# FPGA_Decoupling.net
KiCad netlist of a schematic drawn in Altium Designer
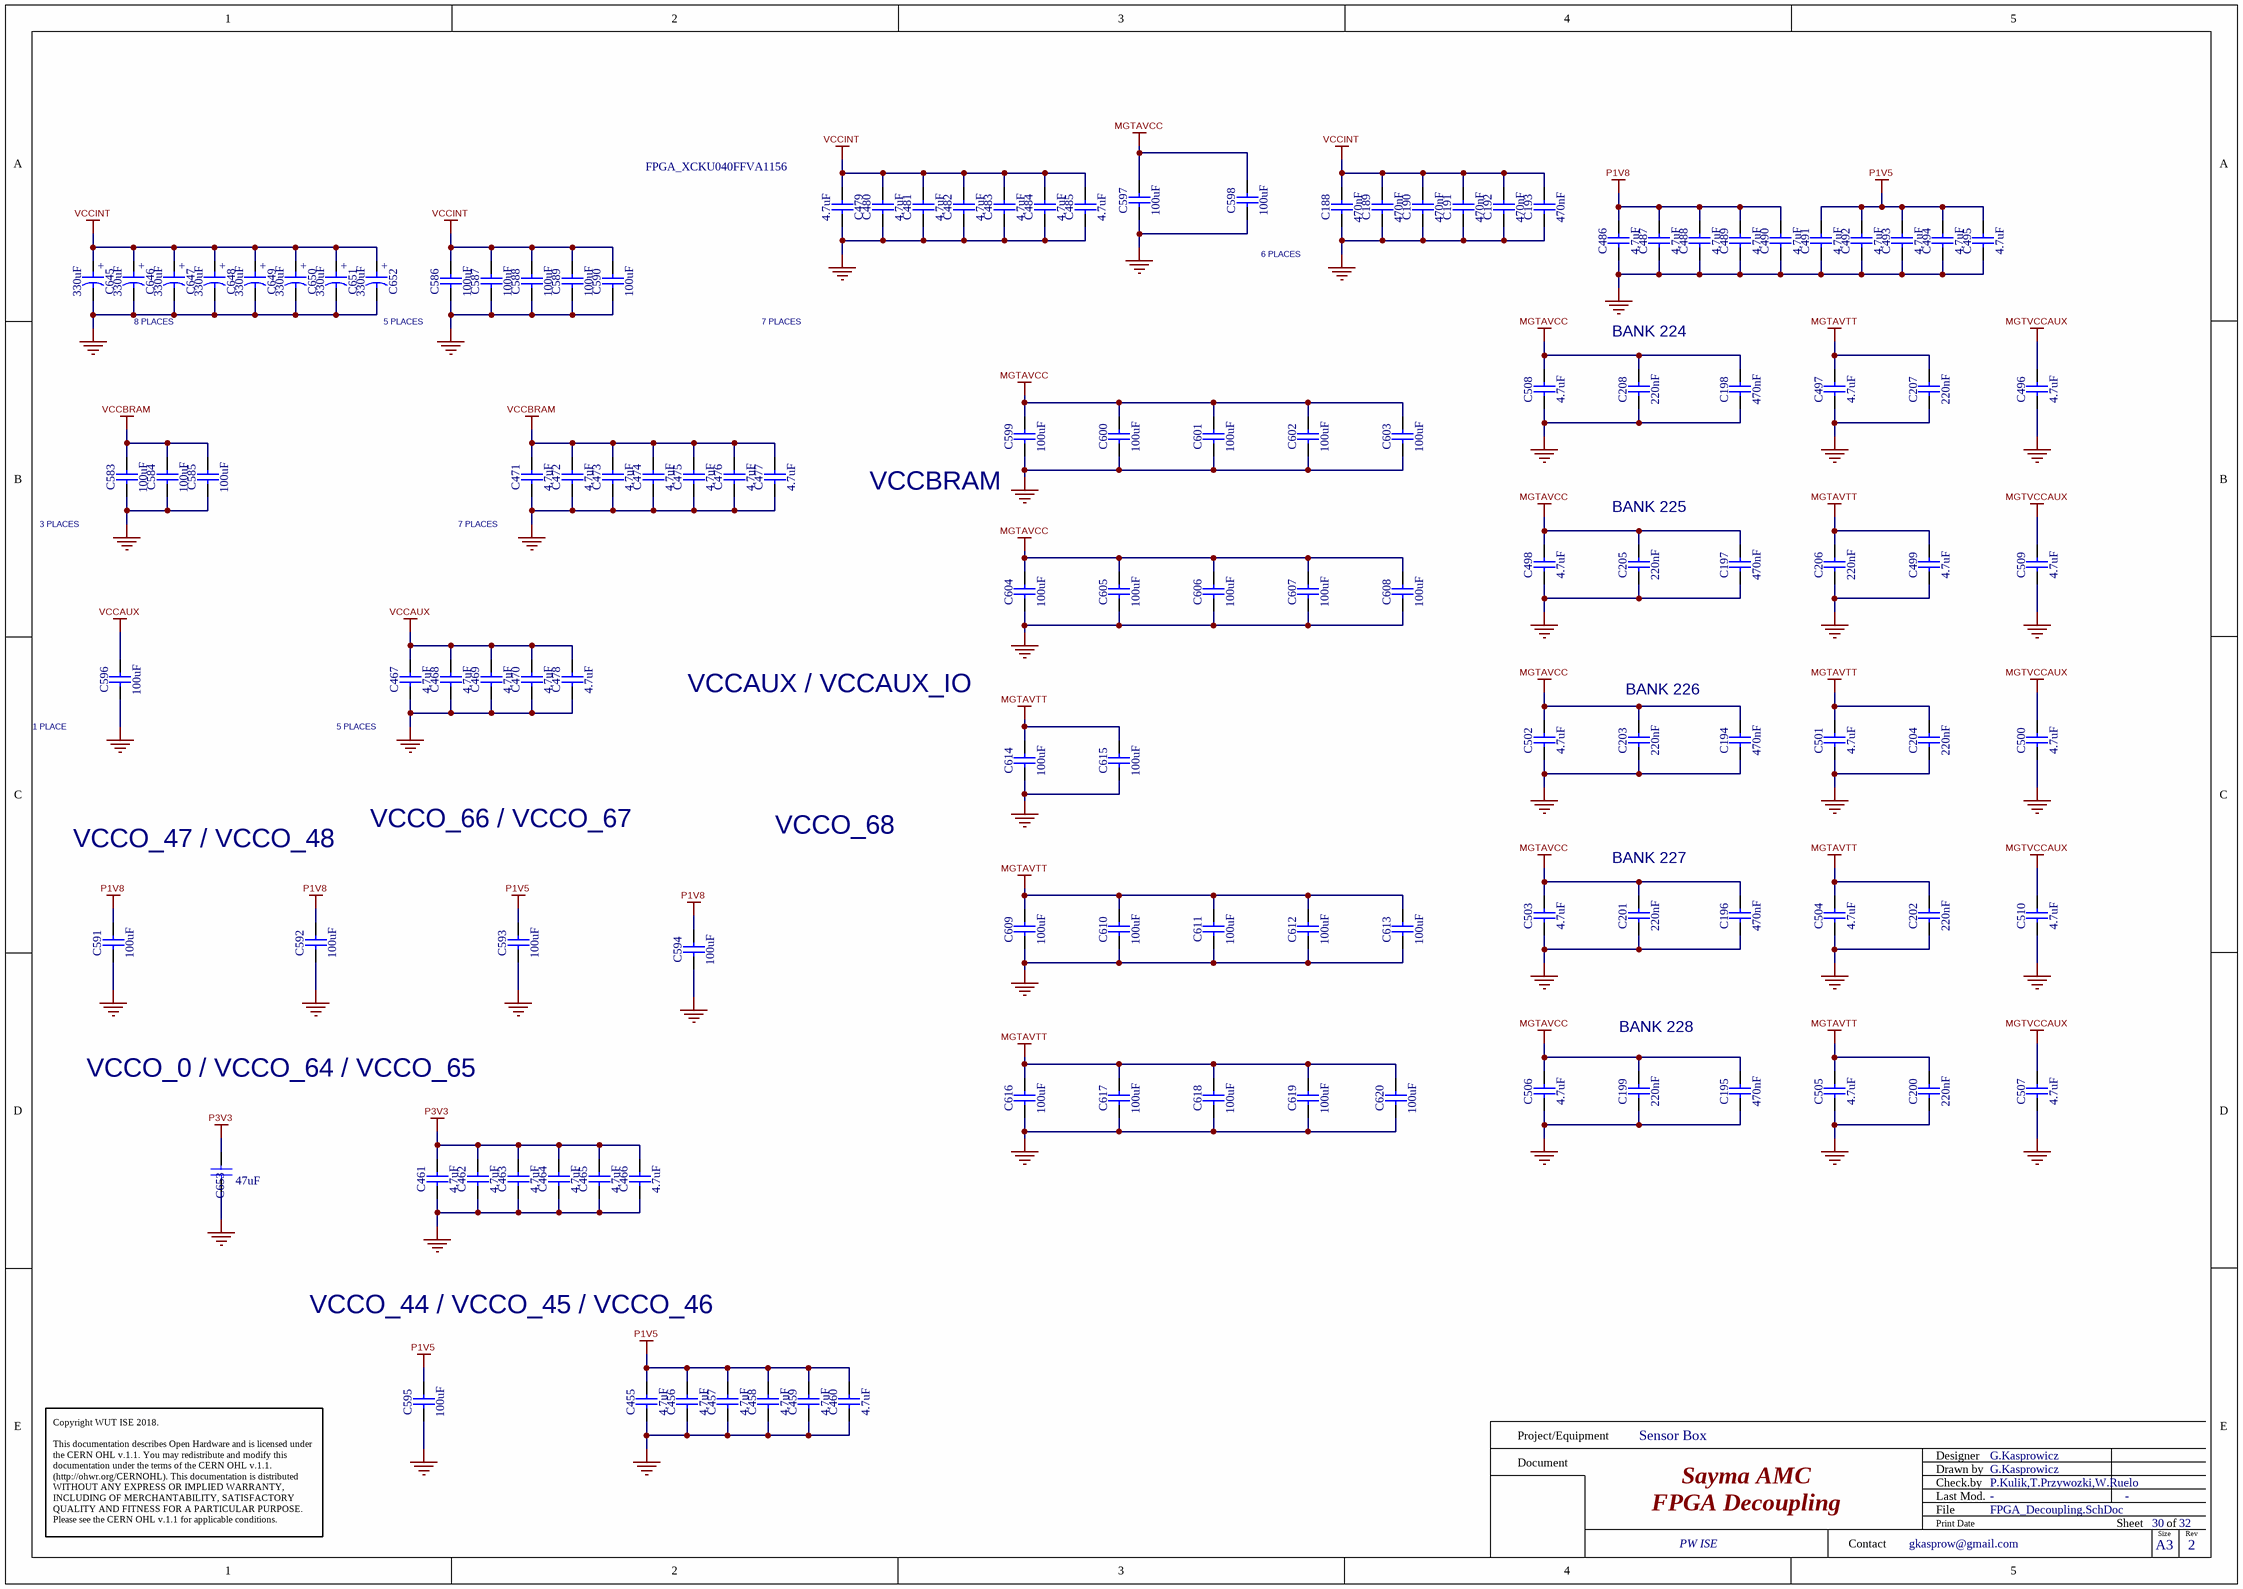
[diagram p0: FPGA_Decoupling.SchDoc]

(export (version "E")
  (design (tool "Eeschema 10.0.6"))
  (components
    (comp (ref "C188")
      (value "470nF")
      (footprint "CAPC0603X33N")
      (description "Non-polarised capacitor")
      (fields
        (field (name "MANUFACTURER PART NUMBER") "CC0201_470NF_4V_20%_X5R")
        (field (name "MANUFACTURER") "GENERIC")
        (field (name "AUTHOR") "CERN DEM JLC")
      )
      (libsource (lib "Capacitors") (part "Capacitor - non polarized"))
    )
    (comp (ref "C189")
      (value "470nF")
      (footprint "CAPC0603X33N")
      (description "Non-polarised capacitor")
      (fields
        (field (name "MANUFACTURER PART NUMBER") "CC0201_470NF_4V_20%_X5R")
        (field (name "MANUFACTURER") "GENERIC")
        (field (name "AUTHOR") "CERN DEM JLC")
      )
      (libsource (lib "Capacitors") (part "Capacitor - non polarized"))
    )
    (comp (ref "C190")
      (value "470nF")
      (footprint "CAPC0603X33N")
      (description "Non-polarised capacitor")
      (fields
        (field (name "MANUFACTURER PART NUMBER") "CC0201_470NF_4V_20%_X5R")
        (field (name "MANUFACTURER") "GENERIC")
        (field (name "AUTHOR") "CERN DEM JLC")
      )
      (libsource (lib "Capacitors") (part "Capacitor - non polarized"))
    )
    (comp (ref "C191")
      (value "470nF")
      (footprint "CAPC0603X33N")
      (description "Non-polarised capacitor")
      (fields
        (field (name "MANUFACTURER PART NUMBER") "CC0201_470NF_4V_20%_X5R")
        (field (name "MANUFACTURER") "GENERIC")
        (field (name "AUTHOR") "CERN DEM JLC")
      )
      (libsource (lib "Capacitors") (part "Capacitor - non polarized"))
    )
    (comp (ref "C192")
      (value "470nF")
      (footprint "CAPC0603X33N")
      (description "Non-polarised capacitor")
      (fields
        (field (name "MANUFACTURER PART NUMBER") "CC0201_470NF_4V_20%_X5R")
        (field (name "MANUFACTURER") "GENERIC")
        (field (name "AUTHOR") "CERN DEM JLC")
      )
      (libsource (lib "Capacitors") (part "Capacitor - non polarized"))
    )
    (comp (ref "C193")
      (value "470nF")
      (footprint "CAPC0603X33N")
      (description "Non-polarised capacitor")
      (fields
        (field (name "MANUFACTURER PART NUMBER") "CC0201_470NF_4V_20%_X5R")
        (field (name "MANUFACTURER") "GENERIC")
        (field (name "AUTHOR") "CERN DEM JLC")
      )
      (libsource (lib "Capacitors") (part "Capacitor - non polarized"))
    )
    (comp (ref "C194")
      (value "470nF")
      (footprint "CAPC0603X33N")
      (description "Non-polarised capacitor")
      (fields
        (field (name "MANUFACTURER PART NUMBER") "CC0201_470NF_4V_20%_X5R")
        (field (name "MANUFACTURER") "GENERIC")
        (field (name "AUTHOR") "CERN DEM JLC")
      )
      (libsource (lib "Capacitors") (part "Capacitor - non polarized"))
    )
    (comp (ref "C195")
      (value "470nF")
      (footprint "CAPC0603X33N")
      (description "Non-polarised capacitor")
      (fields
        (field (name "MANUFACTURER PART NUMBER") "CC0201_470NF_4V_20%_X5R")
        (field (name "MANUFACTURER") "GENERIC")
        (field (name "AUTHOR") "CERN DEM JLC")
      )
      (libsource (lib "Capacitors") (part "Capacitor - non polarized"))
    )
    (comp (ref "C196")
      (value "470nF")
      (footprint "CAPC0603X33N")
      (description "Non-polarised capacitor")
      (fields
        (field (name "MANUFACTURER PART NUMBER") "CC0201_470NF_4V_20%_X5R")
        (field (name "MANUFACTURER") "GENERIC")
        (field (name "AUTHOR") "CERN DEM JLC")
      )
      (libsource (lib "Capacitors") (part "Capacitor - non polarized"))
    )
    (comp (ref "C197")
      (value "470nF")
      (footprint "CAPC0603X33N")
      (description "Non-polarised capacitor")
      (fields
        (field (name "MANUFACTURER PART NUMBER") "CC0201_470NF_4V_20%_X5R")
        (field (name "MANUFACTURER") "GENERIC")
        (field (name "AUTHOR") "CERN DEM JLC")
      )
      (libsource (lib "Capacitors") (part "Capacitor - non polarized"))
    )
    (comp (ref "C198")
      (value "470nF")
      (footprint "CAPC0603X33N")
      (description "Non-polarised capacitor")
      (fields
        (field (name "MANUFACTURER PART NUMBER") "CC0201_470NF_4V_20%_X5R")
        (field (name "MANUFACTURER") "GENERIC")
        (field (name "AUTHOR") "CERN DEM JLC")
      )
      (libsource (lib "Capacitors") (part "Capacitor - non polarized"))
    )
    (comp (ref "C199")
      (value "220nF")
      (footprint "CAPC0603X33N")
      (description "Non-polarised capacitor")
      (fields
        (field (name "MANUFACTURER PART NUMBER") "CC0201_220NF_6.3V_20%_X5R")
        (field (name "MANUFACTURER") "GENERIC")
        (field (name "AUTHOR") "CERN DEM JLC")
      )
      (libsource (lib "Capacitors") (part "Capacitor - non polarized"))
    )
    (comp (ref "C200")
      (value "220nF")
      (footprint "CAPC0603X33N")
      (description "Non-polarised capacitor")
      (fields
        (field (name "MANUFACTURER PART NUMBER") "CC0201_220NF_6.3V_20%_X5R")
        (field (name "MANUFACTURER") "GENERIC")
        (field (name "AUTHOR") "CERN DEM JLC")
      )
      (libsource (lib "Capacitors") (part "Capacitor - non polarized"))
    )
    (comp (ref "C201")
      (value "220nF")
      (footprint "CAPC0603X33N")
      (description "Non-polarised capacitor")
      (fields
        (field (name "MANUFACTURER PART NUMBER") "CC0201_220NF_6.3V_20%_X5R")
        (field (name "MANUFACTURER") "GENERIC")
        (field (name "AUTHOR") "CERN DEM JLC")
      )
      (libsource (lib "Capacitors") (part "Capacitor - non polarized"))
    )
    (comp (ref "C202")
      (value "220nF")
      (footprint "CAPC0603X33N")
      (description "Non-polarised capacitor")
      (fields
        (field (name "MANUFACTURER PART NUMBER") "CC0201_220NF_6.3V_20%_X5R")
        (field (name "MANUFACTURER") "GENERIC")
        (field (name "AUTHOR") "CERN DEM JLC")
      )
      (libsource (lib "Capacitors") (part "Capacitor - non polarized"))
    )
    (comp (ref "C203")
      (value "220nF")
      (footprint "CAPC0603X33N")
      (description "Non-polarised capacitor")
      (fields
        (field (name "MANUFACTURER PART NUMBER") "CC0201_220NF_6.3V_20%_X5R")
        (field (name "MANUFACTURER") "GENERIC")
        (field (name "AUTHOR") "CERN DEM JLC")
      )
      (libsource (lib "Capacitors") (part "Capacitor - non polarized"))
    )
    (comp (ref "C204")
      (value "220nF")
      (footprint "CAPC0603X33N")
      (description "Non-polarised capacitor")
      (fields
        (field (name "MANUFACTURER PART NUMBER") "CC0201_220NF_6.3V_20%_X5R")
        (field (name "MANUFACTURER") "GENERIC")
        (field (name "AUTHOR") "CERN DEM JLC")
      )
      (libsource (lib "Capacitors") (part "Capacitor - non polarized"))
    )
    (comp (ref "C205")
      (value "220nF")
      (footprint "CAPC0603X33N")
      (description "Non-polarised capacitor")
      (fields
        (field (name "MANUFACTURER PART NUMBER") "CC0201_220NF_6.3V_20%_X5R")
        (field (name "MANUFACTURER") "GENERIC")
        (field (name "AUTHOR") "CERN DEM JLC")
      )
      (libsource (lib "Capacitors") (part "Capacitor - non polarized"))
    )
    (comp (ref "C206")
      (value "220nF")
      (footprint "CAPC0603X33N")
      (description "Non-polarised capacitor")
      (fields
        (field (name "MANUFACTURER PART NUMBER") "CC0201_220NF_6.3V_20%_X5R")
        (field (name "MANUFACTURER") "GENERIC")
        (field (name "AUTHOR") "CERN DEM JLC")
      )
      (libsource (lib "Capacitors") (part "Capacitor - non polarized"))
    )
    (comp (ref "C207")
      (value "220nF")
      (footprint "CAPC0603X33N")
      (description "Non-polarised capacitor")
      (fields
        (field (name "MANUFACTURER PART NUMBER") "CC0201_220NF_6.3V_20%_X5R")
        (field (name "MANUFACTURER") "GENERIC")
        (field (name "AUTHOR") "CERN DEM JLC")
      )
      (libsource (lib "Capacitors") (part "Capacitor - non polarized"))
    )
    (comp (ref "C208")
      (value "220nF")
      (footprint "CAPC0603X33N")
      (description "Non-polarised capacitor")
      (fields
        (field (name "MANUFACTURER PART NUMBER") "CC0201_220NF_6.3V_20%_X5R")
        (field (name "MANUFACTURER") "GENERIC")
        (field (name "AUTHOR") "CERN DEM JLC")
      )
      (libsource (lib "Capacitors") (part "Capacitor - non polarized"))
    )
    (comp (ref "C455")
      (value "4.7uF")
      (footprint "CAPC1005X55N")
      (description "Non-polarised capacitor")
      (fields
        (field (name "MANUFACTURER PART NUMBER") "CC0402_4.7UF_6.3V_20%_X5R")
        (field (name "MANUFACTURER") "GENERIC")
        (field (name "AUTHOR") "CERN DEM JLC")
      )
      (libsource (lib "Capacitors") (part "Capacitor - non polarized"))
    )
    (comp (ref "C456")
      (value "4.7uF")
      (footprint "CAPC1005X55N")
      (description "Non-polarised capacitor")
      (fields
        (field (name "MANUFACTURER PART NUMBER") "CC0402_4.7UF_6.3V_20%_X5R")
        (field (name "MANUFACTURER") "GENERIC")
        (field (name "AUTHOR") "CERN DEM JLC")
      )
      (libsource (lib "Capacitors") (part "Capacitor - non polarized"))
    )
    (comp (ref "C457")
      (value "4.7uF")
      (footprint "CAPC1005X55N")
      (description "Non-polarised capacitor")
      (fields
        (field (name "MANUFACTURER PART NUMBER") "CC0402_4.7UF_6.3V_20%_X5R")
        (field (name "MANUFACTURER") "GENERIC")
        (field (name "AUTHOR") "CERN DEM JLC")
      )
      (libsource (lib "Capacitors") (part "Capacitor - non polarized"))
    )
    (comp (ref "C458")
      (value "4.7uF")
      (footprint "CAPC1005X55N")
      (description "Non-polarised capacitor")
      (fields
        (field (name "MANUFACTURER PART NUMBER") "CC0402_4.7UF_6.3V_20%_X5R")
        (field (name "MANUFACTURER") "GENERIC")
        (field (name "AUTHOR") "CERN DEM JLC")
      )
      (libsource (lib "Capacitors") (part "Capacitor - non polarized"))
    )
    (comp (ref "C459")
      (value "4.7uF")
      (footprint "CAPC1005X55N")
      (description "Non-polarised capacitor")
      (fields
        (field (name "MANUFACTURER PART NUMBER") "CC0402_4.7UF_6.3V_20%_X5R")
        (field (name "MANUFACTURER") "GENERIC")
        (field (name "AUTHOR") "CERN DEM JLC")
      )
      (libsource (lib "Capacitors") (part "Capacitor - non polarized"))
    )
    (comp (ref "C460")
      (value "4.7uF")
      (footprint "CAPC1005X55N")
      (description "Non-polarised capacitor")
      (fields
        (field (name "MANUFACTURER PART NUMBER") "CC0402_4.7UF_6.3V_20%_X5R")
        (field (name "MANUFACTURER") "GENERIC")
        (field (name "AUTHOR") "CERN DEM JLC")
      )
      (libsource (lib "Capacitors") (part "Capacitor - non polarized"))
    )
    (comp (ref "C461")
      (value "4.7uF")
      (footprint "CAPC1005X55N")
      (description "Non-polarised capacitor")
      (fields
        (field (name "MANUFACTURER PART NUMBER") "CC0402_4.7UF_6.3V_20%_X5R")
        (field (name "MANUFACTURER") "GENERIC")
        (field (name "AUTHOR") "CERN DEM JLC")
      )
      (libsource (lib "Capacitors") (part "Capacitor - non polarized"))
    )
    (comp (ref "C462")
      (value "4.7uF")
      (footprint "CAPC1005X55N")
      (description "Non-polarised capacitor")
      (fields
        (field (name "MANUFACTURER PART NUMBER") "CC0402_4.7UF_6.3V_20%_X5R")
        (field (name "MANUFACTURER") "GENERIC")
        (field (name "AUTHOR") "CERN DEM JLC")
      )
      (libsource (lib "Capacitors") (part "Capacitor - non polarized"))
    )
    (comp (ref "C463")
      (value "4.7uF")
      (footprint "CAPC1005X55N")
      (description "Non-polarised capacitor")
      (fields
        (field (name "MANUFACTURER PART NUMBER") "CC0402_4.7UF_6.3V_20%_X5R")
        (field (name "MANUFACTURER") "GENERIC")
        (field (name "AUTHOR") "CERN DEM JLC")
      )
      (libsource (lib "Capacitors") (part "Capacitor - non polarized"))
    )
    (comp (ref "C464")
      (value "4.7uF")
      (footprint "CAPC1005X55N")
      (description "Non-polarised capacitor")
      (fields
        (field (name "MANUFACTURER PART NUMBER") "CC0402_4.7UF_6.3V_20%_X5R")
        (field (name "MANUFACTURER") "GENERIC")
        (field (name "AUTHOR") "CERN DEM JLC")
      )
      (libsource (lib "Capacitors") (part "Capacitor - non polarized"))
    )
    (comp (ref "C465")
      (value "4.7uF")
      (footprint "CAPC1005X55N")
      (description "Non-polarised capacitor")
      (fields
        (field (name "MANUFACTURER PART NUMBER") "CC0402_4.7UF_6.3V_20%_X5R")
        (field (name "MANUFACTURER") "GENERIC")
        (field (name "AUTHOR") "CERN DEM JLC")
      )
      (libsource (lib "Capacitors") (part "Capacitor - non polarized"))
    )
    (comp (ref "C466")
      (value "4.7uF")
      (footprint "CAPC1005X55N")
      (description "Non-polarised capacitor")
      (fields
        (field (name "MANUFACTURER PART NUMBER") "CC0402_4.7UF_6.3V_20%_X5R")
        (field (name "MANUFACTURER") "GENERIC")
        (field (name "AUTHOR") "CERN DEM JLC")
      )
      (libsource (lib "Capacitors") (part "Capacitor - non polarized"))
    )
    (comp (ref "C467")
      (value "4.7uF")
      (footprint "CAPC1005X55N")
      (description "Non-polarised capacitor")
      (fields
        (field (name "MANUFACTURER PART NUMBER") "CC0402_4.7UF_6.3V_20%_X5R")
        (field (name "MANUFACTURER") "GENERIC")
        (field (name "AUTHOR") "CERN DEM JLC")
      )
      (libsource (lib "Capacitors") (part "Capacitor - non polarized"))
    )
    (comp (ref "C468")
      (value "4.7uF")
      (footprint "CAPC1005X55N")
      (description "Non-polarised capacitor")
      (fields
        (field (name "MANUFACTURER PART NUMBER") "CC0402_4.7UF_6.3V_20%_X5R")
        (field (name "MANUFACTURER") "GENERIC")
        (field (name "AUTHOR") "CERN DEM JLC")
      )
      (libsource (lib "Capacitors") (part "Capacitor - non polarized"))
    )
    (comp (ref "C469")
      (value "4.7uF")
      (footprint "CAPC1005X55N")
      (description "Non-polarised capacitor")
      (fields
        (field (name "MANUFACTURER PART NUMBER") "CC0402_4.7UF_6.3V_20%_X5R")
        (field (name "MANUFACTURER") "GENERIC")
        (field (name "AUTHOR") "CERN DEM JLC")
      )
      (libsource (lib "Capacitors") (part "Capacitor - non polarized"))
    )
    (comp (ref "C470")
      (value "4.7uF")
      (footprint "CAPC1005X55N")
      (description "Non-polarised capacitor")
      (fields
        (field (name "MANUFACTURER PART NUMBER") "CC0402_4.7UF_6.3V_20%_X5R")
        (field (name "MANUFACTURER") "GENERIC")
        (field (name "AUTHOR") "CERN DEM JLC")
      )
      (libsource (lib "Capacitors") (part "Capacitor - non polarized"))
    )
    (comp (ref "C471")
      (value "4.7uF")
      (footprint "CAPC1005X55N")
      (description "Non-polarised capacitor")
      (fields
        (field (name "MANUFACTURER PART NUMBER") "CC0402_4.7UF_6.3V_20%_X5R")
        (field (name "MANUFACTURER") "GENERIC")
        (field (name "AUTHOR") "CERN DEM JLC")
      )
      (libsource (lib "Capacitors") (part "Capacitor - non polarized"))
    )
    (comp (ref "C472")
      (value "4.7uF")
      (footprint "CAPC1005X55N")
      (description "Non-polarised capacitor")
      (fields
        (field (name "MANUFACTURER PART NUMBER") "CC0402_4.7UF_6.3V_20%_X5R")
        (field (name "MANUFACTURER") "GENERIC")
        (field (name "AUTHOR") "CERN DEM JLC")
      )
      (libsource (lib "Capacitors") (part "Capacitor - non polarized"))
    )
    (comp (ref "C473")
      (value "4.7uF")
      (footprint "CAPC1005X55N")
      (description "Non-polarised capacitor")
      (fields
        (field (name "MANUFACTURER PART NUMBER") "CC0402_4.7UF_6.3V_20%_X5R")
        (field (name "MANUFACTURER") "GENERIC")
        (field (name "AUTHOR") "CERN DEM JLC")
      )
      (libsource (lib "Capacitors") (part "Capacitor - non polarized"))
    )
    (comp (ref "C474")
      (value "4.7uF")
      (footprint "CAPC1005X55N")
      (description "Non-polarised capacitor")
      (fields
        (field (name "MANUFACTURER PART NUMBER") "CC0402_4.7UF_6.3V_20%_X5R")
        (field (name "MANUFACTURER") "GENERIC")
        (field (name "AUTHOR") "CERN DEM JLC")
      )
      (libsource (lib "Capacitors") (part "Capacitor - non polarized"))
    )
    (comp (ref "C475")
      (value "4.7uF")
      (footprint "CAPC1005X55N")
      (description "Non-polarised capacitor")
      (fields
        (field (name "MANUFACTURER PART NUMBER") "CC0402_4.7UF_6.3V_20%_X5R")
        (field (name "MANUFACTURER") "GENERIC")
        (field (name "AUTHOR") "CERN DEM JLC")
      )
      (libsource (lib "Capacitors") (part "Capacitor - non polarized"))
    )
    (comp (ref "C476")
      (value "4.7uF")
      (footprint "CAPC1005X55N")
      (description "Non-polarised capacitor")
      (fields
        (field (name "MANUFACTURER PART NUMBER") "CC0402_4.7UF_6.3V_20%_X5R")
        (field (name "MANUFACTURER") "GENERIC")
        (field (name "AUTHOR") "CERN DEM JLC")
      )
      (libsource (lib "Capacitors") (part "Capacitor - non polarized"))
    )
    (comp (ref "C477")
      (value "4.7uF")
      (footprint "CAPC1005X55N")
      (description "Non-polarised capacitor")
      (fields
        (field (name "MANUFACTURER PART NUMBER") "CC0402_4.7UF_6.3V_20%_X5R")
        (field (name "MANUFACTURER") "GENERIC")
        (field (name "AUTHOR") "CERN DEM JLC")
      )
      (libsource (lib "Capacitors") (part "Capacitor - non polarized"))
    )
    (comp (ref "C478")
      (value "4.7uF")
      (footprint "CAPC1005X55N")
      (description "Non-polarised capacitor")
      (fields
        (field (name "MANUFACTURER PART NUMBER") "CC0402_4.7UF_6.3V_20%_X5R")
        (field (name "MANUFACTURER") "GENERIC")
        (field (name "AUTHOR") "CERN DEM JLC")
      )
      (libsource (lib "Capacitors") (part "Capacitor - non polarized"))
    )
    (comp (ref "C479")
      (value "4.7uF")
      (footprint "CAPC1005X55N")
      (description "Non-polarised capacitor")
      (fields
        (field (name "MANUFACTURER PART NUMBER") "CC0402_4.7UF_6.3V_20%_X5R")
        (field (name "MANUFACTURER") "GENERIC")
        (field (name "AUTHOR") "CERN DEM JLC")
      )
      (libsource (lib "Capacitors") (part "Capacitor - non polarized"))
    )
    (comp (ref "C480")
      (value "4.7uF")
      (footprint "CAPC1005X55N")
      (description "Non-polarised capacitor")
      (fields
        (field (name "MANUFACTURER PART NUMBER") "CC0402_4.7UF_6.3V_20%_X5R")
        (field (name "MANUFACTURER") "GENERIC")
        (field (name "AUTHOR") "CERN DEM JLC")
      )
      (libsource (lib "Capacitors") (part "Capacitor - non polarized"))
    )
    (comp (ref "C481")
      (value "4.7uF")
      (footprint "CAPC1005X55N")
      (description "Non-polarised capacitor")
      (fields
        (field (name "MANUFACTURER PART NUMBER") "CC0402_4.7UF_6.3V_20%_X5R")
        (field (name "MANUFACTURER") "GENERIC")
        (field (name "AUTHOR") "CERN DEM JLC")
      )
      (libsource (lib "Capacitors") (part "Capacitor - non polarized"))
    )
    (comp (ref "C482")
      (value "4.7uF")
      (footprint "CAPC1005X55N")
      (description "Non-polarised capacitor")
      (fields
        (field (name "MANUFACTURER PART NUMBER") "CC0402_4.7UF_6.3V_20%_X5R")
        (field (name "MANUFACTURER") "GENERIC")
        (field (name "AUTHOR") "CERN DEM JLC")
      )
      (libsource (lib "Capacitors") (part "Capacitor - non polarized"))
    )
    (comp (ref "C483")
      (value "4.7uF")
      (footprint "CAPC1005X55N")
      (description "Non-polarised capacitor")
      (fields
        (field (name "MANUFACTURER PART NUMBER") "CC0402_4.7UF_6.3V_20%_X5R")
        (field (name "MANUFACTURER") "GENERIC")
        (field (name "AUTHOR") "CERN DEM JLC")
      )
      (libsource (lib "Capacitors") (part "Capacitor - non polarized"))
    )
    (comp (ref "C484")
      (value "4.7uF")
      (footprint "CAPC1005X55N")
      (description "Non-polarised capacitor")
      (fields
        (field (name "MANUFACTURER PART NUMBER") "CC0402_4.7UF_6.3V_20%_X5R")
        (field (name "MANUFACTURER") "GENERIC")
        (field (name "AUTHOR") "CERN DEM JLC")
      )
      (libsource (lib "Capacitors") (part "Capacitor - non polarized"))
    )
    (comp (ref "C485")
      (value "4.7uF")
      (footprint "CAPC1005X55N")
      (description "Non-polarised capacitor")
      (fields
        (field (name "MANUFACTURER PART NUMBER") "CC0402_4.7UF_6.3V_20%_X5R")
        (field (name "MANUFACTURER") "GENERIC")
        (field (name "AUTHOR") "CERN DEM JLC")
      )
      (libsource (lib "Capacitors") (part "Capacitor - non polarized"))
    )
    (comp (ref "C486")
      (value "4.7uF")
      (footprint "CAPC1005X55N")
      (description "Non-polarised capacitor")
      (fields
        (field (name "MANUFACTURER PART NUMBER") "CC0402_4.7UF_6.3V_20%_X5R")
        (field (name "MANUFACTURER") "GENERIC")
        (field (name "AUTHOR") "CERN DEM JLC")
      )
      (libsource (lib "Capacitors") (part "Capacitor - non polarized"))
    )
    (comp (ref "C487")
      (value "4.7uF")
      (footprint "CAPC1005X55N")
      (description "Non-polarised capacitor")
      (fields
        (field (name "MANUFACTURER PART NUMBER") "CC0402_4.7UF_6.3V_20%_X5R")
        (field (name "MANUFACTURER") "GENERIC")
        (field (name "AUTHOR") "CERN DEM JLC")
      )
      (libsource (lib "Capacitors") (part "Capacitor - non polarized"))
    )
    (comp (ref "C488")
      (value "4.7uF")
      (footprint "CAPC1005X55N")
      (description "Non-polarised capacitor")
      (fields
        (field (name "MANUFACTURER PART NUMBER") "CC0402_4.7UF_6.3V_20%_X5R")
        (field (name "MANUFACTURER") "GENERIC")
        (field (name "AUTHOR") "CERN DEM JLC")
      )
      (libsource (lib "Capacitors") (part "Capacitor - non polarized"))
    )
    (comp (ref "C489")
      (value "4.7uF")
      (footprint "CAPC1005X55N")
      (description "Non-polarised capacitor")
      (fields
        (field (name "MANUFACTURER PART NUMBER") "CC0402_4.7UF_6.3V_20%_X5R")
        (field (name "MANUFACTURER") "GENERIC")
        (field (name "AUTHOR") "CERN DEM JLC")
      )
      (libsource (lib "Capacitors") (part "Capacitor - non polarized"))
    )
    (comp (ref "C490")
      (value "4.7uF")
      (footprint "CAPC1005X55N")
      (description "Non-polarised capacitor")
      (fields
        (field (name "MANUFACTURER PART NUMBER") "CC0402_4.7UF_6.3V_20%_X5R")
        (field (name "MANUFACTURER") "GENERIC")
        (field (name "AUTHOR") "CERN DEM JLC")
      )
      (libsource (lib "Capacitors") (part "Capacitor - non polarized"))
    )
    (comp (ref "C491")
      (value "4.7uF")
      (footprint "CAPC1005X55N")
      (description "Non-polarised capacitor")
      (fields
        (field (name "MANUFACTURER PART NUMBER") "CC0402_4.7UF_6.3V_20%_X5R")
        (field (name "MANUFACTURER") "GENERIC")
        (field (name "AUTHOR") "CERN DEM JLC")
      )
      (libsource (lib "Capacitors") (part "Capacitor - non polarized"))
    )
    (comp (ref "C492")
      (value "4.7uF")
      (footprint "CAPC1005X55N")
      (description "Non-polarised capacitor")
      (fields
        (field (name "MANUFACTURER PART NUMBER") "CC0402_4.7UF_6.3V_20%_X5R")
        (field (name "MANUFACTURER") "GENERIC")
        (field (name "AUTHOR") "CERN DEM JLC")
      )
      (libsource (lib "Capacitors") (part "Capacitor - non polarized"))
    )
    (comp (ref "C493")
      (value "4.7uF")
      (footprint "CAPC1005X55N")
      (description "Non-polarised capacitor")
      (fields
        (field (name "MANUFACTURER PART NUMBER") "CC0402_4.7UF_6.3V_20%_X5R")
        (field (name "MANUFACTURER") "GENERIC")
        (field (name "AUTHOR") "CERN DEM JLC")
      )
      (libsource (lib "Capacitors") (part "Capacitor - non polarized"))
    )
    (comp (ref "C494")
      (value "4.7uF")
      (footprint "CAPC1005X55N")
      (description "Non-polarised capacitor")
      (fields
        (field (name "MANUFACTURER PART NUMBER") "CC0402_4.7UF_6.3V_20%_X5R")
        (field (name "MANUFACTURER") "GENERIC")
        (field (name "AUTHOR") "CERN DEM JLC")
      )
      (libsource (lib "Capacitors") (part "Capacitor - non polarized"))
    )
    (comp (ref "C495")
      (value "4.7uF")
      (footprint "CAPC1005X55N")
      (description "Non-polarised capacitor")
      (fields
        (field (name "MANUFACTURER PART NUMBER") "CC0402_4.7UF_6.3V_20%_X5R")
        (field (name "MANUFACTURER") "GENERIC")
        (field (name "AUTHOR") "CERN DEM JLC")
      )
      (libsource (lib "Capacitors") (part "Capacitor - non polarized"))
    )
    (comp (ref "C496")
      (value "4.7uF")
      (footprint "CAPC1005X55N")
      (description "Non-polarised capacitor")
      (fields
        (field (name "MANUFACTURER PART NUMBER") "CC0402_4.7UF_6.3V_20%_X5R")
        (field (name "MANUFACTURER") "GENERIC")
        (field (name "AUTHOR") "CERN DEM JLC")
      )
      (libsource (lib "Capacitors") (part "Capacitor - non polarized"))
    )
    (comp (ref "C497")
      (value "4.7uF")
      (footprint "CAPC1005X55N")
      (description "Non-polarised capacitor")
      (fields
        (field (name "MANUFACTURER PART NUMBER") "CC0402_4.7UF_6.3V_20%_X5R")
        (field (name "MANUFACTURER") "GENERIC")
        (field (name "AUTHOR") "CERN DEM JLC")
      )
      (libsource (lib "Capacitors") (part "Capacitor - non polarized"))
    )
    (comp (ref "C498")
      (value "4.7uF")
      (footprint "CAPC1005X55N")
      (description "Non-polarised capacitor")
      (fields
        (field (name "MANUFACTURER PART NUMBER") "CC0402_4.7UF_6.3V_20%_X5R")
        (field (name "MANUFACTURER") "GENERIC")
        (field (name "AUTHOR") "CERN DEM JLC")
      )
      (libsource (lib "Capacitors") (part "Capacitor - non polarized"))
    )
    (comp (ref "C499")
      (value "4.7uF")
      (footprint "CAPC1005X55N")
      (description "Non-polarised capacitor")
      (fields
        (field (name "MANUFACTURER PART NUMBER") "CC0402_4.7UF_6.3V_20%_X5R")
        (field (name "MANUFACTURER") "GENERIC")
        (field (name "AUTHOR") "CERN DEM JLC")
      )
      (libsource (lib "Capacitors") (part "Capacitor - non polarized"))
    )
    (comp (ref "C500")
      (value "4.7uF")
      (footprint "CAPC1005X55N")
      (description "Non-polarised capacitor")
      (fields
        (field (name "MANUFACTURER PART NUMBER") "CC0402_4.7UF_6.3V_20%_X5R")
        (field (name "MANUFACTURER") "GENERIC")
        (field (name "AUTHOR") "CERN DEM JLC")
      )
      (libsource (lib "Capacitors") (part "Capacitor - non polarized"))
    )
    (comp (ref "C501")
      (value "4.7uF")
      (footprint "CAPC1005X55N")
      (description "Non-polarised capacitor")
      (fields
        (field (name "MANUFACTURER PART NUMBER") "CC0402_4.7UF_6.3V_20%_X5R")
        (field (name "MANUFACTURER") "GENERIC")
        (field (name "AUTHOR") "CERN DEM JLC")
      )
      (libsource (lib "Capacitors") (part "Capacitor - non polarized"))
    )
    (comp (ref "C502")
      (value "4.7uF")
      (footprint "CAPC1005X55N")
      (description "Non-polarised capacitor")
      (fields
        (field (name "MANUFACTURER PART NUMBER") "CC0402_4.7UF_6.3V_20%_X5R")
        (field (name "MANUFACTURER") "GENERIC")
        (field (name "AUTHOR") "CERN DEM JLC")
      )
      (libsource (lib "Capacitors") (part "Capacitor - non polarized"))
    )
    (comp (ref "C503")
      (value "4.7uF")
      (footprint "CAPC1005X55N")
      (description "Non-polarised capacitor")
      (fields
        (field (name "MANUFACTURER PART NUMBER") "CC0402_4.7UF_6.3V_20%_X5R")
        (field (name "MANUFACTURER") "GENERIC")
        (field (name "AUTHOR") "CERN DEM JLC")
      )
      (libsource (lib "Capacitors") (part "Capacitor - non polarized"))
    )
    (comp (ref "C504")
      (value "4.7uF")
      (footprint "CAPC1005X55N")
      (description "Non-polarised capacitor")
      (fields
        (field (name "MANUFACTURER PART NUMBER") "CC0402_4.7UF_6.3V_20%_X5R")
        (field (name "MANUFACTURER") "GENERIC")
        (field (name "AUTHOR") "CERN DEM JLC")
      )
      (libsource (lib "Capacitors") (part "Capacitor - non polarized"))
    )
    (comp (ref "C505")
      (value "4.7uF")
      (footprint "CAPC1005X55N")
      (description "Non-polarised capacitor")
      (fields
        (field (name "MANUFACTURER PART NUMBER") "CC0402_4.7UF_6.3V_20%_X5R")
        (field (name "MANUFACTURER") "GENERIC")
        (field (name "AUTHOR") "CERN DEM JLC")
      )
      (libsource (lib "Capacitors") (part "Capacitor - non polarized"))
    )
    (comp (ref "C506")
      (value "4.7uF")
      (footprint "CAPC1005X55N")
      (description "Non-polarised capacitor")
      (fields
        (field (name "MANUFACTURER PART NUMBER") "CC0402_4.7UF_6.3V_20%_X5R")
        (field (name "MANUFACTURER") "GENERIC")
        (field (name "AUTHOR") "CERN DEM JLC")
      )
      (libsource (lib "Capacitors") (part "Capacitor - non polarized"))
    )
    (comp (ref "C507")
      (value "4.7uF")
      (footprint "CAPC1005X55N")
      (description "Non-polarised capacitor")
      (fields
        (field (name "MANUFACTURER PART NUMBER") "CC0402_4.7UF_6.3V_20%_X5R")
        (field (name "MANUFACTURER") "GENERIC")
        (field (name "AUTHOR") "CERN DEM JLC")
      )
      (libsource (lib "Capacitors") (part "Capacitor - non polarized"))
    )
    (comp (ref "C508")
      (value "4.7uF")
      (footprint "CAPC1005X55N")
      (description "Non-polarised capacitor")
      (fields
        (field (name "MANUFACTURER PART NUMBER") "CC0402_4.7UF_6.3V_20%_X5R")
        (field (name "MANUFACTURER") "GENERIC")
        (field (name "AUTHOR") "CERN DEM JLC")
      )
      (libsource (lib "Capacitors") (part "Capacitor - non polarized"))
    )
    (comp (ref "C509")
      (value "4.7uF")
      (footprint "CAPC1005X55N")
      (description "Non-polarised capacitor")
      (fields
        (field (name "MANUFACTURER PART NUMBER") "CC0402_4.7UF_6.3V_20%_X5R")
        (field (name "MANUFACTURER") "GENERIC")
        (field (name "AUTHOR") "CERN DEM JLC")
      )
      (libsource (lib "Capacitors") (part "Capacitor - non polarized"))
    )
    (comp (ref "C510")
      (value "4.7uF")
      (footprint "CAPC1005X55N")
      (description "Non-polarised capacitor")
      (fields
        (field (name "MANUFACTURER PART NUMBER") "CC0402_4.7UF_6.3V_20%_X5R")
        (field (name "MANUFACTURER") "GENERIC")
        (field (name "AUTHOR") "CERN DEM JLC")
      )
      (libsource (lib "Capacitors") (part "Capacitor - non polarized"))
    )
    (comp (ref "C583")
      (value "100uF")
      (footprint "CAPC3216X180N")
      (description "Non-polarised capacitor")
      (fields
        (field (name "MANUFACTURER PART NUMBER") "CC1206_100UF_6.3V_20%_X5R")
        (field (name "MANUFACTURER") "GENERIC")
        (field (name "AUTHOR") "CERN DEM JLC")
      )
      (libsource (lib "Capacitors") (part "Capacitor - non polarized"))
    )
    (comp (ref "C584")
      (value "100uF")
      (footprint "CAPC3216X180N")
      (description "Non-polarised capacitor")
      (fields
        (field (name "MANUFACTURER PART NUMBER") "CC1206_100UF_6.3V_20%_X5R")
        (field (name "MANUFACTURER") "GENERIC")
        (field (name "AUTHOR") "CERN DEM JLC")
      )
      (libsource (lib "Capacitors") (part "Capacitor - non polarized"))
    )
    (comp (ref "C585")
      (value "100uF")
      (footprint "CAPC3216X180N")
      (description "Non-polarised capacitor")
      (fields
        (field (name "MANUFACTURER PART NUMBER") "CC1206_100UF_6.3V_20%_X5R")
        (field (name "MANUFACTURER") "GENERIC")
        (field (name "AUTHOR") "CERN DEM JLC")
      )
      (libsource (lib "Capacitors") (part "Capacitor - non polarized"))
    )
    (comp (ref "C586")
      (value "100uF")
      (footprint "CAPC3216X180N")
      (description "Non-polarised capacitor")
      (fields
        (field (name "MANUFACTURER PART NUMBER") "CC1206_100UF_6.3V_20%_X5R")
        (field (name "MANUFACTURER") "GENERIC")
        (field (name "AUTHOR") "CERN DEM JLC")
      )
      (libsource (lib "Capacitors") (part "Capacitor - non polarized"))
    )
    (comp (ref "C587")
      (value "100uF")
      (footprint "CAPC3216X180N")
      (description "Non-polarised capacitor")
      (fields
        (field (name "MANUFACTURER PART NUMBER") "CC1206_100UF_6.3V_20%_X5R")
        (field (name "MANUFACTURER") "GENERIC")
        (field (name "AUTHOR") "CERN DEM JLC")
      )
      (libsource (lib "Capacitors") (part "Capacitor - non polarized"))
    )
    (comp (ref "C588")
      (value "100uF")
      (footprint "CAPC3216X180N")
      (description "Non-polarised capacitor")
      (fields
        (field (name "MANUFACTURER PART NUMBER") "CC1206_100UF_6.3V_20%_X5R")
        (field (name "MANUFACTURER") "GENERIC")
        (field (name "AUTHOR") "CERN DEM JLC")
      )
      (libsource (lib "Capacitors") (part "Capacitor - non polarized"))
    )
    (comp (ref "C589")
      (value "100uF")
      (footprint "CAPC3216X180N")
      (description "Non-polarised capacitor")
      (fields
        (field (name "MANUFACTURER PART NUMBER") "CC1206_100UF_6.3V_20%_X5R")
        (field (name "MANUFACTURER") "GENERIC")
        (field (name "AUTHOR") "CERN DEM JLC")
      )
      (libsource (lib "Capacitors") (part "Capacitor - non polarized"))
    )
    (comp (ref "C590")
      (value "100uF")
      (footprint "CAPC3216X180N")
      (description "Non-polarised capacitor")
      (fields
        (field (name "MANUFACTURER PART NUMBER") "CC1206_100UF_6.3V_20%_X5R")
        (field (name "MANUFACTURER") "GENERIC")
        (field (name "AUTHOR") "CERN DEM JLC")
      )
      (libsource (lib "Capacitors") (part "Capacitor - non polarized"))
    )
    (comp (ref "C591")
      (value "100uF")
      (footprint "CAPC3216X180N")
      (description "Non-polarised capacitor")
      (fields
        (field (name "MANUFACTURER PART NUMBER") "CC1206_100UF_6.3V_20%_X5R")
        (field (name "MANUFACTURER") "GENERIC")
        (field (name "AUTHOR") "CERN DEM JLC")
      )
      (libsource (lib "Capacitors") (part "Capacitor - non polarized"))
    )
    (comp (ref "C592")
      (value "100uF")
      (footprint "CAPC3216X180N")
      (description "Non-polarised capacitor")
      (fields
        (field (name "MANUFACTURER PART NUMBER") "CC1206_100UF_6.3V_20%_X5R")
        (field (name "MANUFACTURER") "GENERIC")
        (field (name "AUTHOR") "CERN DEM JLC")
      )
      (libsource (lib "Capacitors") (part "Capacitor - non polarized"))
    )
    (comp (ref "C593")
      (value "100uF")
      (footprint "CAPC3216X180N")
      (description "Non-polarised capacitor")
      (fields
        (field (name "MANUFACTURER PART NUMBER") "CC1206_100UF_6.3V_20%_X5R")
        (field (name "MANUFACTURER") "GENERIC")
        (field (name "AUTHOR") "CERN DEM JLC")
      )
      (libsource (lib "Capacitors") (part "Capacitor - non polarized"))
    )
    (comp (ref "C594")
      (value "100uF")
      (footprint "CAPC3216X180N")
      (description "Non-polarised capacitor")
      (fields
        (field (name "MANUFACTURER PART NUMBER") "CC1206_100UF_6.3V_20%_X5R")
        (field (name "MANUFACTURER") "GENERIC")
        (field (name "AUTHOR") "CERN DEM JLC")
      )
      (libsource (lib "Capacitors") (part "Capacitor - non polarized"))
    )
    (comp (ref "C595")
      (value "100uF")
      (footprint "CAPC3216X180N")
      (description "Non-polarised capacitor")
      (fields
        (field (name "MANUFACTURER PART NUMBER") "CC1206_100UF_6.3V_20%_X5R")
        (field (name "MANUFACTURER") "GENERIC")
        (field (name "AUTHOR") "CERN DEM JLC")
      )
      (libsource (lib "Capacitors") (part "Capacitor - non polarized"))
    )
    (comp (ref "C596")
      (value "100uF")
      (footprint "CAPC3216X180N")
      (description "Non-polarised capacitor")
      (fields
        (field (name "MANUFACTURER PART NUMBER") "CC1206_100UF_6.3V_20%_X5R")
        (field (name "MANUFACTURER") "GENERIC")
        (field (name "AUTHOR") "CERN DEM JLC")
      )
      (libsource (lib "Capacitors") (part "Capacitor - non polarized"))
    )
    (comp (ref "C597")
      (value "100uF")
      (footprint "CAPC3216X180N")
      (description "Non-polarised capacitor")
      (fields
        (field (name "MANUFACTURER PART NUMBER") "CC1206_100UF_6.3V_20%_X5R")
        (field (name "MANUFACTURER") "GENERIC")
        (field (name "AUTHOR") "CERN DEM JLC")
      )
      (libsource (lib "Capacitors") (part "Capacitor - non polarized"))
    )
    (comp (ref "C598")
      (value "100uF")
      (footprint "CAPC3216X180N")
      (description "Non-polarised capacitor")
      (fields
        (field (name "MANUFACTURER PART NUMBER") "CC1206_100UF_6.3V_20%_X5R")
        (field (name "MANUFACTURER") "GENERIC")
        (field (name "AUTHOR") "CERN DEM JLC")
      )
      (libsource (lib "Capacitors") (part "Capacitor - non polarized"))
    )
    (comp (ref "C599")
      (value "100uF")
      (footprint "CAPC3216X180N")
      (description "Non-polarised capacitor")
      (fields
        (field (name "MANUFACTURER PART NUMBER") "CC1206_100UF_6.3V_20%_X5R")
        (field (name "MANUFACTURER") "GENERIC")
        (field (name "AUTHOR") "CERN DEM JLC")
      )
      (libsource (lib "Capacitors") (part "Capacitor - non polarized"))
    )
    (comp (ref "C600")
      (value "100uF")
      (footprint "CAPC3216X180N")
      (description "Non-polarised capacitor")
      (fields
        (field (name "MANUFACTURER PART NUMBER") "CC1206_100UF_6.3V_20%_X5R")
        (field (name "MANUFACTURER") "GENERIC")
        (field (name "AUTHOR") "CERN DEM JLC")
      )
      (libsource (lib "Capacitors") (part "Capacitor - non polarized"))
    )
    (comp (ref "C601")
      (value "100uF")
      (footprint "CAPC3216X180N")
      (description "Non-polarised capacitor")
      (fields
        (field (name "MANUFACTURER PART NUMBER") "CC1206_100UF_6.3V_20%_X5R")
        (field (name "MANUFACTURER") "GENERIC")
        (field (name "AUTHOR") "CERN DEM JLC")
      )
      (libsource (lib "Capacitors") (part "Capacitor - non polarized"))
    )
    (comp (ref "C602")
      (value "100uF")
      (footprint "CAPC3216X180N")
      (description "Non-polarised capacitor")
      (fields
        (field (name "MANUFACTURER PART NUMBER") "CC1206_100UF_6.3V_20%_X5R")
        (field (name "MANUFACTURER") "GENERIC")
        (field (name "AUTHOR") "CERN DEM JLC")
      )
      (libsource (lib "Capacitors") (part "Capacitor - non polarized"))
    )
    (comp (ref "C603")
      (value "100uF")
      (footprint "CAPC3216X180N")
      (description "Non-polarised capacitor")
      (fields
        (field (name "MANUFACTURER PART NUMBER") "CC1206_100UF_6.3V_20%_X5R")
        (field (name "MANUFACTURER") "GENERIC")
        (field (name "AUTHOR") "CERN DEM JLC")
      )
      (libsource (lib "Capacitors") (part "Capacitor - non polarized"))
    )
    (comp (ref "C604")
      (value "100uF")
      (footprint "CAPC3216X180N")
      (description "Non-polarised capacitor")
      (fields
        (field (name "MANUFACTURER PART NUMBER") "CC1206_100UF_6.3V_20%_X5R")
        (field (name "MANUFACTURER") "GENERIC")
        (field (name "AUTHOR") "CERN DEM JLC")
      )
      (libsource (lib "Capacitors") (part "Capacitor - non polarized"))
    )
    (comp (ref "C605")
      (value "100uF")
      (footprint "CAPC3216X180N")
      (description "Non-polarised capacitor")
      (fields
        (field (name "MANUFACTURER PART NUMBER") "CC1206_100UF_6.3V_20%_X5R")
        (field (name "MANUFACTURER") "GENERIC")
        (field (name "AUTHOR") "CERN DEM JLC")
      )
      (libsource (lib "Capacitors") (part "Capacitor - non polarized"))
    )
    (comp (ref "C606")
      (value "100uF")
      (footprint "CAPC3216X180N")
      (description "Non-polarised capacitor")
      (fields
        (field (name "MANUFACTURER PART NUMBER") "CC1206_100UF_6.3V_20%_X5R")
        (field (name "MANUFACTURER") "GENERIC")
        (field (name "AUTHOR") "CERN DEM JLC")
      )
      (libsource (lib "Capacitors") (part "Capacitor - non polarized"))
    )
    (comp (ref "C607")
      (value "100uF")
      (footprint "CAPC3216X180N")
      (description "Non-polarised capacitor")
      (fields
        (field (name "MANUFACTURER PART NUMBER") "CC1206_100UF_6.3V_20%_X5R")
        (field (name "MANUFACTURER") "GENERIC")
        (field (name "AUTHOR") "CERN DEM JLC")
      )
      (libsource (lib "Capacitors") (part "Capacitor - non polarized"))
    )
    (comp (ref "C608")
      (value "100uF")
      (footprint "CAPC3216X180N")
      (description "Non-polarised capacitor")
      (fields
        (field (name "MANUFACTURER PART NUMBER") "CC1206_100UF_6.3V_20%_X5R")
        (field (name "MANUFACTURER") "GENERIC")
        (field (name "AUTHOR") "CERN DEM JLC")
      )
      (libsource (lib "Capacitors") (part "Capacitor - non polarized"))
    )
    (comp (ref "C609")
      (value "100uF")
      (footprint "CAPC3216X180N")
      (description "Non-polarised capacitor")
      (fields
        (field (name "MANUFACTURER PART NUMBER") "CC1206_100UF_6.3V_20%_X5R")
        (field (name "MANUFACTURER") "GENERIC")
        (field (name "AUTHOR") "CERN DEM JLC")
      )
      (libsource (lib "Capacitors") (part "Capacitor - non polarized"))
    )
    (comp (ref "C610")
      (value "100uF")
      (footprint "CAPC3216X180N")
      (description "Non-polarised capacitor")
      (fields
        (field (name "MANUFACTURER PART NUMBER") "CC1206_100UF_6.3V_20%_X5R")
        (field (name "MANUFACTURER") "GENERIC")
        (field (name "AUTHOR") "CERN DEM JLC")
      )
      (libsource (lib "Capacitors") (part "Capacitor - non polarized"))
    )
    (comp (ref "C611")
      (value "100uF")
      (footprint "CAPC3216X180N")
      (description "Non-polarised capacitor")
      (fields
        (field (name "MANUFACTURER PART NUMBER") "CC1206_100UF_6.3V_20%_X5R")
        (field (name "MANUFACTURER") "GENERIC")
        (field (name "AUTHOR") "CERN DEM JLC")
      )
      (libsource (lib "Capacitors") (part "Capacitor - non polarized"))
    )
    (comp (ref "C612")
      (value "100uF")
      (footprint "CAPC3216X180N")
      (description "Non-polarised capacitor")
      (fields
        (field (name "MANUFACTURER PART NUMBER") "CC1206_100UF_6.3V_20%_X5R")
        (field (name "MANUFACTURER") "GENERIC")
        (field (name "AUTHOR") "CERN DEM JLC")
      )
      (libsource (lib "Capacitors") (part "Capacitor - non polarized"))
    )
    (comp (ref "C613")
      (value "100uF")
      (footprint "CAPC3216X180N")
      (description "Non-polarised capacitor")
      (fields
        (field (name "MANUFACTURER PART NUMBER") "CC1206_100UF_6.3V_20%_X5R")
        (field (name "MANUFACTURER") "GENERIC")
        (field (name "AUTHOR") "CERN DEM JLC")
      )
      (libsource (lib "Capacitors") (part "Capacitor - non polarized"))
    )
    (comp (ref "C614")
      (value "100uF")
      (footprint "CAPC3216X180N")
      (description "Non-polarised capacitor")
      (fields
        (field (name "MANUFACTURER PART NUMBER") "CC1206_100UF_6.3V_20%_X5R")
        (field (name "MANUFACTURER") "GENERIC")
        (field (name "AUTHOR") "CERN DEM JLC")
      )
      (libsource (lib "Capacitors") (part "Capacitor - non polarized"))
    )
    (comp (ref "C615")
      (value "100uF")
      (footprint "CAPC3216X180N")
      (description "Non-polarised capacitor")
      (fields
        (field (name "MANUFACTURER PART NUMBER") "CC1206_100UF_6.3V_20%_X5R")
        (field (name "MANUFACTURER") "GENERIC")
        (field (name "AUTHOR") "CERN DEM JLC")
      )
      (libsource (lib "Capacitors") (part "Capacitor - non polarized"))
    )
    (comp (ref "C616")
      (value "100uF")
      (footprint "CAPC3216X180N")
      (description "Non-polarised capacitor")
      (fields
        (field (name "MANUFACTURER PART NUMBER") "CC1206_100UF_6.3V_20%_X5R")
        (field (name "MANUFACTURER") "GENERIC")
        (field (name "AUTHOR") "CERN DEM JLC")
      )
      (libsource (lib "Capacitors") (part "Capacitor - non polarized"))
    )
    (comp (ref "C617")
      (value "100uF")
      (footprint "CAPC3216X180N")
      (description "Non-polarised capacitor")
      (fields
        (field (name "MANUFACTURER PART NUMBER") "CC1206_100UF_6.3V_20%_X5R")
        (field (name "MANUFACTURER") "GENERIC")
        (field (name "AUTHOR") "CERN DEM JLC")
      )
      (libsource (lib "Capacitors") (part "Capacitor - non polarized"))
    )
    (comp (ref "C618")
      (value "100uF")
      (footprint "CAPC3216X180N")
      (description "Non-polarised capacitor")
      (fields
        (field (name "MANUFACTURER PART NUMBER") "CC1206_100UF_6.3V_20%_X5R")
        (field (name "MANUFACTURER") "GENERIC")
        (field (name "AUTHOR") "CERN DEM JLC")
      )
      (libsource (lib "Capacitors") (part "Capacitor - non polarized"))
    )
    (comp (ref "C619")
      (value "100uF")
      (footprint "CAPC3216X180N")
      (description "Non-polarised capacitor")
      (fields
        (field (name "MANUFACTURER PART NUMBER") "CC1206_100UF_6.3V_20%_X5R")
        (field (name "MANUFACTURER") "GENERIC")
        (field (name "AUTHOR") "CERN DEM JLC")
      )
      (libsource (lib "Capacitors") (part "Capacitor - non polarized"))
    )
    (comp (ref "C620")
      (value "100uF")
      (footprint "CAPC3216X180N")
      (description "Non-polarised capacitor")
      (fields
        (field (name "MANUFACTURER PART NUMBER") "CC1206_100UF_6.3V_20%_X5R")
        (field (name "MANUFACTURER") "GENERIC")
        (field (name "AUTHOR") "CERN DEM JLC")
      )
      (libsource (lib "Capacitors") (part "Capacitor - non polarized"))
    )
    (comp (ref "C645")
      (value "330uF")
      (footprint "CAPMP3528X210N")
      (description "Polarised capacitor")
      (fields
        (field (name "MANUFACTURER PART NUMBER") "T520B337M2R5ATE015")
        (field (name "MANUFACTURER") "KEMET")
        (field (name "AUTHOR") "CERN DEM JLC")
      )
      (libsource (lib "Capacitors") (part "Capacitor - polarized"))
    )
    (comp (ref "C646")
      (value "330uF")
      (footprint "CAPMP3528X210N")
      (description "Polarised capacitor")
      (fields
        (field (name "MANUFACTURER PART NUMBER") "T520B337M2R5ATE015")
        (field (name "MANUFACTURER") "KEMET")
        (field (name "AUTHOR") "CERN DEM JLC")
      )
      (libsource (lib "Capacitors") (part "Capacitor - polarized"))
    )
    (comp (ref "C647")
      (value "330uF")
      (footprint "CAPMP3528X210N")
      (description "Polarised capacitor")
      (fields
        (field (name "MANUFACTURER PART NUMBER") "T520B337M2R5ATE015")
        (field (name "MANUFACTURER") "KEMET")
        (field (name "AUTHOR") "CERN DEM JLC")
      )
      (libsource (lib "Capacitors") (part "Capacitor - polarized"))
    )
    (comp (ref "C648")
      (value "330uF")
      (footprint "CAPMP3528X210N")
      (description "Polarised capacitor")
      (fields
        (field (name "MANUFACTURER PART NUMBER") "T520B337M2R5ATE015")
        (field (name "MANUFACTURER") "KEMET")
        (field (name "AUTHOR") "CERN DEM JLC")
      )
      (libsource (lib "Capacitors") (part "Capacitor - polarized"))
    )
    (comp (ref "C649")
      (value "330uF")
      (footprint "CAPMP3528X210N")
      (description "Polarised capacitor")
      (fields
        (field (name "MANUFACTURER PART NUMBER") "T520B337M2R5ATE015")
        (field (name "MANUFACTURER") "KEMET")
        (field (name "AUTHOR") "CERN DEM JLC")
      )
      (libsource (lib "Capacitors") (part "Capacitor - polarized"))
    )
    (comp (ref "C650")
      (value "330uF")
      (footprint "CAPMP3528X210N")
      (description "Polarised capacitor")
      (fields
        (field (name "MANUFACTURER PART NUMBER") "T520B337M2R5ATE015")
        (field (name "MANUFACTURER") "KEMET")
        (field (name "AUTHOR") "CERN DEM JLC")
      )
      (libsource (lib "Capacitors") (part "Capacitor - polarized"))
    )
    (comp (ref "C651")
      (value "330uF")
      (footprint "CAPMP3528X210N")
      (description "Polarised capacitor")
      (fields
        (field (name "MANUFACTURER PART NUMBER") "T520B337M2R5ATE015")
        (field (name "MANUFACTURER") "KEMET")
        (field (name "AUTHOR") "CERN DEM JLC")
      )
      (libsource (lib "Capacitors") (part "Capacitor - polarized"))
    )
    (comp (ref "C652")
      (value "330uF")
      (footprint "CAPMP3528X210N")
      (description "Polarised capacitor")
      (fields
        (field (name "MANUFACTURER PART NUMBER") "T520B337M2R5ATE015")
        (field (name "MANUFACTURER") "KEMET")
        (field (name "AUTHOR") "CERN DEM JLC")
      )
      (libsource (lib "Capacitors") (part "Capacitor - polarized"))
    )
    (comp (ref "C653")
      (value "47uF")
      (footprint "CAPC3225X270N")
      (fields
        (field (name "$$NOTCOMMONPROPERTY_GENERAL PART NUMBER") "CC1210_47UF_6.3V_10%_X5R")
        (field (name "$$NOTCOMMONPROPERTY_MANUFACTURER1 PART NUMBER") "12106D476KAT2A")
        (field (name "MANUFACTURER") "GENERIC")
      )
      (libsource (lib "altium-import") (part "root_1__*"))
    )
  )
  (nets
    (net (code "1") (name "GND") (class "Default")
      (node (ref "C188") (pin "1") (pinfunction "1_1") (pintype "passive"))
      (node (ref "C189") (pin "1") (pinfunction "1_1") (pintype "passive"))
      (node (ref "C190") (pin "1") (pinfunction "1_1") (pintype "passive"))
      (node (ref "C191") (pin "1") (pinfunction "1_1") (pintype "passive"))
      (node (ref "C192") (pin "1") (pinfunction "1_1") (pintype "passive"))
      (node (ref "C193") (pin "1") (pinfunction "1_1") (pintype "passive"))
      (node (ref "C194") (pin "1") (pinfunction "1_1") (pintype "passive"))
      (node (ref "C195") (pin "1") (pinfunction "1_1") (pintype "passive"))
      (node (ref "C196") (pin "1") (pinfunction "1_1") (pintype "passive"))
      (node (ref "C197") (pin "1") (pinfunction "1_1") (pintype "passive"))
      (node (ref "C198") (pin "1") (pinfunction "1_1") (pintype "passive"))
      (node (ref "C199") (pin "1") (pinfunction "1_1") (pintype "passive"))
      (node (ref "C200") (pin "1") (pinfunction "1_1") (pintype "passive"))
      (node (ref "C201") (pin "1") (pinfunction "1_1") (pintype "passive"))
      (node (ref "C202") (pin "1") (pinfunction "1_1") (pintype "passive"))
      (node (ref "C203") (pin "1") (pinfunction "1_1") (pintype "passive"))
      (node (ref "C204") (pin "1") (pinfunction "1_1") (pintype "passive"))
      (node (ref "C205") (pin "1") (pinfunction "1_1") (pintype "passive"))
      (node (ref "C206") (pin "1") (pinfunction "1_1") (pintype "passive"))
      (node (ref "C207") (pin "1") (pinfunction "1_1") (pintype "passive"))
      (node (ref "C208") (pin "1") (pinfunction "1_1") (pintype "passive"))
      (node (ref "C455") (pin "1") (pinfunction "1_1") (pintype "passive"))
      (node (ref "C456") (pin "1") (pinfunction "1_1") (pintype "passive"))
      (node (ref "C457") (pin "1") (pinfunction "1_1") (pintype "passive"))
      (node (ref "C458") (pin "1") (pinfunction "1_1") (pintype "passive"))
      (node (ref "C459") (pin "1") (pinfunction "1_1") (pintype "passive"))
      (node (ref "C460") (pin "1") (pinfunction "1_1") (pintype "passive"))
      (node (ref "C461") (pin "1") (pinfunction "1_1") (pintype "passive"))
      (node (ref "C462") (pin "1") (pinfunction "1_1") (pintype "passive"))
      (node (ref "C463") (pin "1") (pinfunction "1_1") (pintype "passive"))
      (node (ref "C464") (pin "1") (pinfunction "1_1") (pintype "passive"))
      (node (ref "C465") (pin "1") (pinfunction "1_1") (pintype "passive"))
      (node (ref "C466") (pin "1") (pinfunction "1_1") (pintype "passive"))
      (node (ref "C467") (pin "1") (pinfunction "1_1") (pintype "passive"))
      (node (ref "C468") (pin "1") (pinfunction "1_1") (pintype "passive"))
      (node (ref "C469") (pin "1") (pinfunction "1_1") (pintype "passive"))
      (node (ref "C470") (pin "1") (pinfunction "1_1") (pintype "passive"))
      (node (ref "C471") (pin "1") (pinfunction "1_1") (pintype "passive"))
      (node (ref "C472") (pin "1") (pinfunction "1_1") (pintype "passive"))
      (node (ref "C473") (pin "1") (pinfunction "1_1") (pintype "passive"))
      (node (ref "C474") (pin "1") (pinfunction "1_1") (pintype "passive"))
      (node (ref "C475") (pin "1") (pinfunction "1_1") (pintype "passive"))
      (node (ref "C476") (pin "1") (pinfunction "1_1") (pintype "passive"))
      (node (ref "C477") (pin "1") (pinfunction "1_1") (pintype "passive"))
      (node (ref "C478") (pin "1") (pinfunction "1_1") (pintype "passive"))
      (node (ref "C479") (pin "1") (pinfunction "1_1") (pintype "passive"))
      (node (ref "C480") (pin "1") (pinfunction "1_1") (pintype "passive"))
      (node (ref "C481") (pin "1") (pinfunction "1_1") (pintype "passive"))
      (node (ref "C482") (pin "1") (pinfunction "1_1") (pintype "passive"))
      (node (ref "C483") (pin "1") (pinfunction "1_1") (pintype "passive"))
      (node (ref "C484") (pin "1") (pinfunction "1_1") (pintype "passive"))
      (node (ref "C485") (pin "1") (pinfunction "1_1") (pintype "passive"))
      (node (ref "C486") (pin "1") (pinfunction "1_1") (pintype "passive"))
      (node (ref "C487") (pin "1") (pinfunction "1_1") (pintype "passive"))
      (node (ref "C488") (pin "1") (pinfunction "1_1") (pintype "passive"))
      (node (ref "C489") (pin "1") (pinfunction "1_1") (pintype "passive"))
      (node (ref "C490") (pin "1") (pinfunction "1_1") (pintype "passive"))
      (node (ref "C491") (pin "1") (pinfunction "1_1") (pintype "passive"))
      (node (ref "C492") (pin "1") (pinfunction "1_1") (pintype "passive"))
      (node (ref "C493") (pin "1") (pinfunction "1_1") (pintype "passive"))
      (node (ref "C494") (pin "1") (pinfunction "1_1") (pintype "passive"))
      (node (ref "C495") (pin "1") (pinfunction "1_1") (pintype "passive"))
      (node (ref "C496") (pin "1") (pinfunction "1_1") (pintype "passive"))
      (node (ref "C497") (pin "1") (pinfunction "1_1") (pintype "passive"))
      (node (ref "C498") (pin "1") (pinfunction "1_1") (pintype "passive"))
      (node (ref "C499") (pin "1") (pinfunction "1_1") (pintype "passive"))
      (node (ref "C500") (pin "1") (pinfunction "1_1") (pintype "passive"))
      (node (ref "C501") (pin "1") (pinfunction "1_1") (pintype "passive"))
      (node (ref "C502") (pin "1") (pinfunction "1_1") (pintype "passive"))
      (node (ref "C503") (pin "1") (pinfunction "1_1") (pintype "passive"))
      (node (ref "C504") (pin "1") (pinfunction "1_1") (pintype "passive"))
      (node (ref "C505") (pin "1") (pinfunction "1_1") (pintype "passive"))
      (node (ref "C506") (pin "1") (pinfunction "1_1") (pintype "passive"))
      (node (ref "C507") (pin "1") (pinfunction "1_1") (pintype "passive"))
      (node (ref "C508") (pin "1") (pinfunction "1_1") (pintype "passive"))
      (node (ref "C509") (pin "1") (pinfunction "1_1") (pintype "passive"))
      (node (ref "C510") (pin "1") (pinfunction "1_1") (pintype "passive"))
      (node (ref "C583") (pin "1") (pinfunction "1_1") (pintype "passive"))
      (node (ref "C584") (pin "1") (pinfunction "1_1") (pintype "passive"))
      (node (ref "C585") (pin "1") (pinfunction "1_1") (pintype "passive"))
      (node (ref "C586") (pin "1") (pinfunction "1_1") (pintype "passive"))
      (node (ref "C587") (pin "1") (pinfunction "1_1") (pintype "passive"))
      (node (ref "C588") (pin "1") (pinfunction "1_1") (pintype "passive"))
      (node (ref "C589") (pin "1") (pinfunction "1_1") (pintype "passive"))
      (node (ref "C590") (pin "1") (pinfunction "1_1") (pintype "passive"))
      (node (ref "C591") (pin "1") (pinfunction "1_1") (pintype "passive"))
      (node (ref "C592") (pin "1") (pinfunction "1_1") (pintype "passive"))
      (node (ref "C593") (pin "1") (pinfunction "1_1") (pintype "passive"))
      (node (ref "C594") (pin "1") (pinfunction "1_1") (pintype "passive"))
      (node (ref "C595") (pin "1") (pinfunction "1_1") (pintype "passive"))
      (node (ref "C596") (pin "1") (pinfunction "1_1") (pintype "passive"))
      (node (ref "C597") (pin "1") (pinfunction "1_1") (pintype "passive"))
      (node (ref "C598") (pin "1") (pinfunction "1_1") (pintype "passive"))
      (node (ref "C599") (pin "1") (pinfunction "1_1") (pintype "passive"))
      (node (ref "C600") (pin "1") (pinfunction "1_1") (pintype "passive"))
      (node (ref "C601") (pin "1") (pinfunction "1_1") (pintype "passive"))
      (node (ref "C602") (pin "1") (pinfunction "1_1") (pintype "passive"))
      (node (ref "C603") (pin "1") (pinfunction "1_1") (pintype "passive"))
      (node (ref "C604") (pin "1") (pinfunction "1_1") (pintype "passive"))
      (node (ref "C605") (pin "1") (pinfunction "1_1") (pintype "passive"))
      (node (ref "C606") (pin "1") (pinfunction "1_1") (pintype "passive"))
      (node (ref "C607") (pin "1") (pinfunction "1_1") (pintype "passive"))
      (node (ref "C608") (pin "1") (pinfunction "1_1") (pintype "passive"))
      (node (ref "C609") (pin "1") (pinfunction "1_1") (pintype "passive"))
      (node (ref "C610") (pin "1") (pinfunction "1_1") (pintype "passive"))
      (node (ref "C611") (pin "1") (pinfunction "1_1") (pintype "passive"))
      (node (ref "C612") (pin "1") (pinfunction "1_1") (pintype "passive"))
      (node (ref "C613") (pin "1") (pinfunction "1_1") (pintype "passive"))
      (node (ref "C614") (pin "1") (pinfunction "1_1") (pintype "passive"))
      (node (ref "C615") (pin "1") (pinfunction "1_1") (pintype "passive"))
      (node (ref "C616") (pin "1") (pinfunction "1_1") (pintype "passive"))
      (node (ref "C617") (pin "1") (pinfunction "1_1") (pintype "passive"))
      (node (ref "C618") (pin "1") (pinfunction "1_1") (pintype "passive"))
      (node (ref "C619") (pin "1") (pinfunction "1_1") (pintype "passive"))
      (node (ref "C620") (pin "1") (pinfunction "1_1") (pintype "passive"))
      (node (ref "C645") (pin "2") (pinfunction "2_2") (pintype "passive"))
      (node (ref "C646") (pin "2") (pinfunction "2_2") (pintype "passive"))
      (node (ref "C647") (pin "2") (pinfunction "2_2") (pintype "passive"))
      (node (ref "C648") (pin "2") (pinfunction "2_2") (pintype "passive"))
      (node (ref "C649") (pin "2") (pinfunction "2_2") (pintype "passive"))
      (node (ref "C650") (pin "2") (pinfunction "2_2") (pintype "passive"))
      (node (ref "C651") (pin "2") (pinfunction "2_2") (pintype "passive"))
      (node (ref "C652") (pin "2") (pinfunction "2_2") (pintype "passive"))
      (node (ref "C653") (pin "1") (pinfunction "1_1") (pintype "passive"))
    )
    (net (code "2") (name "MGTAVCC") (class "Default")
      (node (ref "C194") (pin "2") (pinfunction "2_2") (pintype "passive"))
      (node (ref "C195") (pin "2") (pinfunction "2_2") (pintype "passive"))
      (node (ref "C196") (pin "2") (pinfunction "2_2") (pintype "passive"))
      (node (ref "C197") (pin "2") (pinfunction "2_2") (pintype "passive"))
      (node (ref "C198") (pin "2") (pinfunction "2_2") (pintype "passive"))
      (node (ref "C199") (pin "2") (pinfunction "2_2") (pintype "passive"))
      (node (ref "C201") (pin "2") (pinfunction "2_2") (pintype "passive"))
      (node (ref "C203") (pin "2") (pinfunction "2_2") (pintype "passive"))
      (node (ref "C205") (pin "2") (pinfunction "2_2") (pintype "passive"))
      (node (ref "C208") (pin "2") (pinfunction "2_2") (pintype "passive"))
      (node (ref "C498") (pin "2") (pinfunction "2_2") (pintype "passive"))
      (node (ref "C502") (pin "2") (pinfunction "2_2") (pintype "passive"))
      (node (ref "C503") (pin "2") (pinfunction "2_2") (pintype "passive"))
      (node (ref "C506") (pin "2") (pinfunction "2_2") (pintype "passive"))
      (node (ref "C508") (pin "2") (pinfunction "2_2") (pintype "passive"))
      (node (ref "C597") (pin "2") (pinfunction "2_2") (pintype "passive"))
      (node (ref "C598") (pin "2") (pinfunction "2_2") (pintype "passive"))
      (node (ref "C599") (pin "2") (pinfunction "2_2") (pintype "passive"))
      (node (ref "C600") (pin "2") (pinfunction "2_2") (pintype "passive"))
      (node (ref "C601") (pin "2") (pinfunction "2_2") (pintype "passive"))
      (node (ref "C602") (pin "2") (pinfunction "2_2") (pintype "passive"))
      (node (ref "C603") (pin "2") (pinfunction "2_2") (pintype "passive"))
      (node (ref "C604") (pin "2") (pinfunction "2_2") (pintype "passive"))
      (node (ref "C605") (pin "2") (pinfunction "2_2") (pintype "passive"))
      (node (ref "C606") (pin "2") (pinfunction "2_2") (pintype "passive"))
      (node (ref "C607") (pin "2") (pinfunction "2_2") (pintype "passive"))
      (node (ref "C608") (pin "2") (pinfunction "2_2") (pintype "passive"))
    )
    (net (code "3") (name "MGTAVTT") (class "Default")
      (node (ref "C200") (pin "2") (pinfunction "2_2") (pintype "passive"))
      (node (ref "C202") (pin "2") (pinfunction "2_2") (pintype "passive"))
      (node (ref "C204") (pin "2") (pinfunction "2_2") (pintype "passive"))
      (node (ref "C206") (pin "2") (pinfunction "2_2") (pintype "passive"))
      (node (ref "C207") (pin "2") (pinfunction "2_2") (pintype "passive"))
      (node (ref "C497") (pin "2") (pinfunction "2_2") (pintype "passive"))
      (node (ref "C499") (pin "2") (pinfunction "2_2") (pintype "passive"))
      (node (ref "C501") (pin "2") (pinfunction "2_2") (pintype "passive"))
      (node (ref "C504") (pin "2") (pinfunction "2_2") (pintype "passive"))
      (node (ref "C505") (pin "2") (pinfunction "2_2") (pintype "passive"))
      (node (ref "C609") (pin "2") (pinfunction "2_2") (pintype "passive"))
      (node (ref "C610") (pin "2") (pinfunction "2_2") (pintype "passive"))
      (node (ref "C611") (pin "2") (pinfunction "2_2") (pintype "passive"))
      (node (ref "C612") (pin "2") (pinfunction "2_2") (pintype "passive"))
      (node (ref "C613") (pin "2") (pinfunction "2_2") (pintype "passive"))
      (node (ref "C614") (pin "2") (pinfunction "2_2") (pintype "passive"))
      (node (ref "C615") (pin "2") (pinfunction "2_2") (pintype "passive"))
      (node (ref "C616") (pin "2") (pinfunction "2_2") (pintype "passive"))
      (node (ref "C617") (pin "2") (pinfunction "2_2") (pintype "passive"))
      (node (ref "C618") (pin "2") (pinfunction "2_2") (pintype "passive"))
      (node (ref "C619") (pin "2") (pinfunction "2_2") (pintype "passive"))
      (node (ref "C620") (pin "2") (pinfunction "2_2") (pintype "passive"))
    )
    (net (code "4") (name "MGTVCCAUX") (class "Default")
      (node (ref "C496") (pin "2") (pinfunction "2_2") (pintype "passive"))
      (node (ref "C500") (pin "2") (pinfunction "2_2") (pintype "passive"))
      (node (ref "C507") (pin "2") (pinfunction "2_2") (pintype "passive"))
      (node (ref "C509") (pin "2") (pinfunction "2_2") (pintype "passive"))
      (node (ref "C510") (pin "2") (pinfunction "2_2") (pintype "passive"))
    )
    (net (code "5") (name "P1V5") (class "Default")
      (node (ref "C455") (pin "2") (pinfunction "2_2") (pintype "passive"))
      (node (ref "C456") (pin "2") (pinfunction "2_2") (pintype "passive"))
      (node (ref "C457") (pin "2") (pinfunction "2_2") (pintype "passive"))
      (node (ref "C458") (pin "2") (pinfunction "2_2") (pintype "passive"))
      (node (ref "C459") (pin "2") (pinfunction "2_2") (pintype "passive"))
      (node (ref "C460") (pin "2") (pinfunction "2_2") (pintype "passive"))
      (node (ref "C491") (pin "2") (pinfunction "2_2") (pintype "passive"))
      (node (ref "C492") (pin "2") (pinfunction "2_2") (pintype "passive"))
      (node (ref "C493") (pin "2") (pinfunction "2_2") (pintype "passive"))
      (node (ref "C494") (pin "2") (pinfunction "2_2") (pintype "passive"))
      (node (ref "C495") (pin "2") (pinfunction "2_2") (pintype "passive"))
      (node (ref "C593") (pin "2") (pinfunction "2_2") (pintype "passive"))
      (node (ref "C595") (pin "2") (pinfunction "2_2") (pintype "passive"))
    )
    (net (code "6") (name "P1V8") (class "Default")
      (node (ref "C486") (pin "2") (pinfunction "2_2") (pintype "passive"))
      (node (ref "C487") (pin "2") (pinfunction "2_2") (pintype "passive"))
      (node (ref "C488") (pin "2") (pinfunction "2_2") (pintype "passive"))
      (node (ref "C489") (pin "2") (pinfunction "2_2") (pintype "passive"))
      (node (ref "C490") (pin "2") (pinfunction "2_2") (pintype "passive"))
      (node (ref "C591") (pin "2") (pinfunction "2_2") (pintype "passive"))
      (node (ref "C592") (pin "2") (pinfunction "2_2") (pintype "passive"))
      (node (ref "C594") (pin "2") (pinfunction "2_2") (pintype "passive"))
    )
    (net (code "7") (name "P3V3") (class "Default")
      (node (ref "C461") (pin "2") (pinfunction "2_2") (pintype "passive"))
      (node (ref "C462") (pin "2") (pinfunction "2_2") (pintype "passive"))
      (node (ref "C463") (pin "2") (pinfunction "2_2") (pintype "passive"))
      (node (ref "C464") (pin "2") (pinfunction "2_2") (pintype "passive"))
      (node (ref "C465") (pin "2") (pinfunction "2_2") (pintype "passive"))
      (node (ref "C466") (pin "2") (pinfunction "2_2") (pintype "passive"))
      (node (ref "C653") (pin "2") (pinfunction "2_2") (pintype "passive"))
    )
    (net (code "8") (name "VCCAUX") (class "Default")
      (node (ref "C467") (pin "2") (pinfunction "2_2") (pintype "passive"))
      (node (ref "C468") (pin "2") (pinfunction "2_2") (pintype "passive"))
      (node (ref "C469") (pin "2") (pinfunction "2_2") (pintype "passive"))
      (node (ref "C470") (pin "2") (pinfunction "2_2") (pintype "passive"))
      (node (ref "C478") (pin "2") (pinfunction "2_2") (pintype "passive"))
      (node (ref "C596") (pin "2") (pinfunction "2_2") (pintype "passive"))
    )
    (net (code "9") (name "VCCBRAM") (class "Default")
      (node (ref "C471") (pin "2") (pinfunction "2_2") (pintype "passive"))
      (node (ref "C472") (pin "2") (pinfunction "2_2") (pintype "passive"))
      (node (ref "C473") (pin "2") (pinfunction "2_2") (pintype "passive"))
      (node (ref "C474") (pin "2") (pinfunction "2_2") (pintype "passive"))
      (node (ref "C475") (pin "2") (pinfunction "2_2") (pintype "passive"))
      (node (ref "C476") (pin "2") (pinfunction "2_2") (pintype "passive"))
      (node (ref "C477") (pin "2") (pinfunction "2_2") (pintype "passive"))
      (node (ref "C583") (pin "2") (pinfunction "2_2") (pintype "passive"))
      (node (ref "C584") (pin "2") (pinfunction "2_2") (pintype "passive"))
      (node (ref "C585") (pin "2") (pinfunction "2_2") (pintype "passive"))
    )
    (net (code "10") (name "VCCINT") (class "Default")
      (node (ref "C188") (pin "2") (pinfunction "2_2") (pintype "passive"))
      (node (ref "C189") (pin "2") (pinfunction "2_2") (pintype "passive"))
      (node (ref "C190") (pin "2") (pinfunction "2_2") (pintype "passive"))
      (node (ref "C191") (pin "2") (pinfunction "2_2") (pintype "passive"))
      (node (ref "C192") (pin "2") (pinfunction "2_2") (pintype "passive"))
      (node (ref "C193") (pin "2") (pinfunction "2_2") (pintype "passive"))
      (node (ref "C479") (pin "2") (pinfunction "2_2") (pintype "passive"))
      (node (ref "C480") (pin "2") (pinfunction "2_2") (pintype "passive"))
      (node (ref "C481") (pin "2") (pinfunction "2_2") (pintype "passive"))
      (node (ref "C482") (pin "2") (pinfunction "2_2") (pintype "passive"))
      (node (ref "C483") (pin "2") (pinfunction "2_2") (pintype "passive"))
      (node (ref "C484") (pin "2") (pinfunction "2_2") (pintype "passive"))
      (node (ref "C485") (pin "2") (pinfunction "2_2") (pintype "passive"))
      (node (ref "C586") (pin "2") (pinfunction "2_2") (pintype "passive"))
      (node (ref "C587") (pin "2") (pinfunction "2_2") (pintype "passive"))
      (node (ref "C588") (pin "2") (pinfunction "2_2") (pintype "passive"))
      (node (ref "C589") (pin "2") (pinfunction "2_2") (pintype "passive"))
      (node (ref "C590") (pin "2") (pinfunction "2_2") (pintype "passive"))
      (node (ref "C645") (pin "1") (pinfunction "1_1") (pintype "passive"))
      (node (ref "C646") (pin "1") (pinfunction "1_1") (pintype "passive"))
      (node (ref "C647") (pin "1") (pinfunction "1_1") (pintype "passive"))
      (node (ref "C648") (pin "1") (pinfunction "1_1") (pintype "passive"))
      (node (ref "C649") (pin "1") (pinfunction "1_1") (pintype "passive"))
      (node (ref "C650") (pin "1") (pinfunction "1_1") (pintype "passive"))
      (node (ref "C651") (pin "1") (pinfunction "1_1") (pintype "passive"))
      (node (ref "C652") (pin "1") (pinfunction "1_1") (pintype "passive"))
    )
  )
)
